# Prototipo_2_0.net
KiCad netlist of a schematic drawn in EAGLE
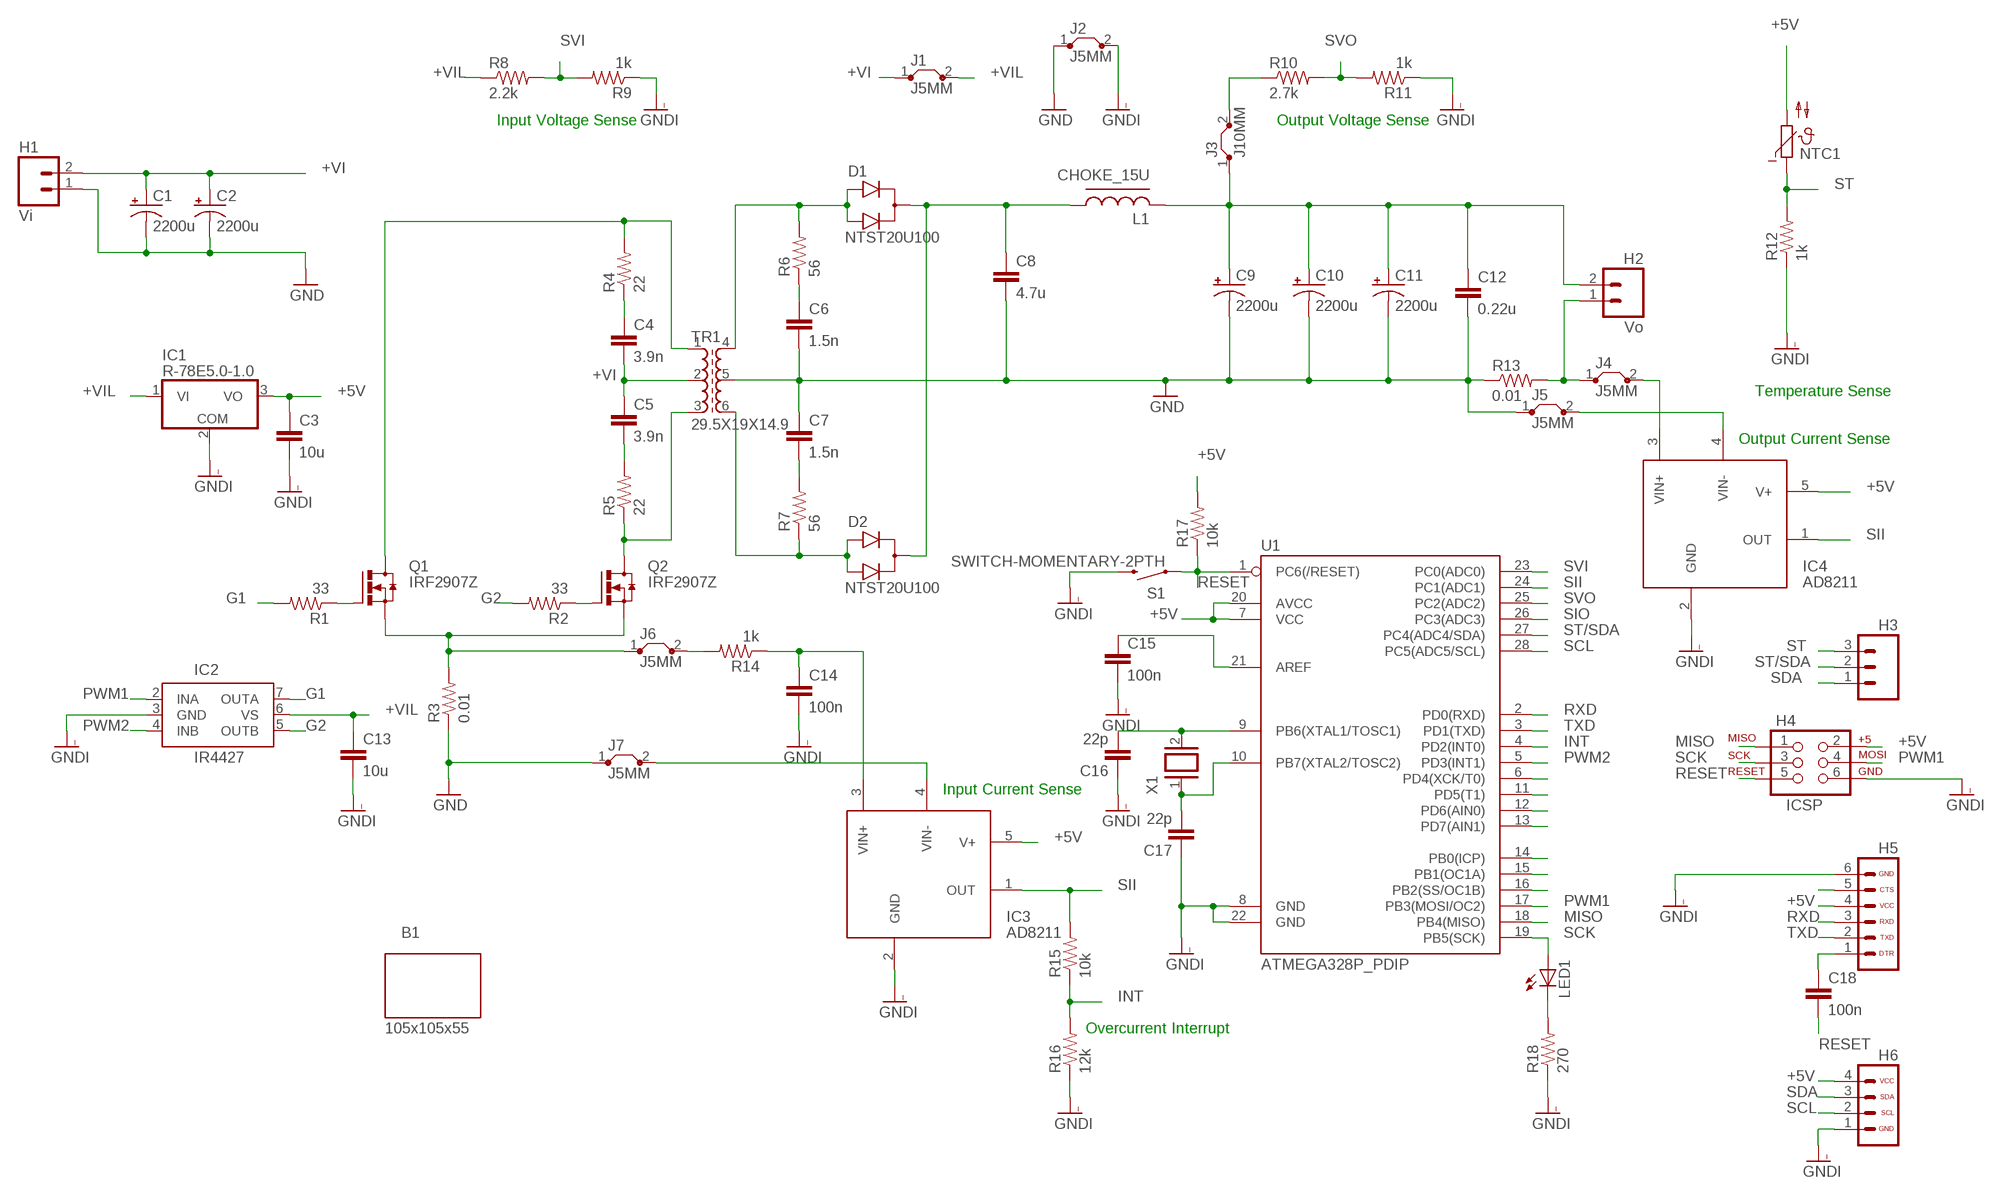
[diagram p0: schematic, sheet 1]

(export (version "E")
  (design (tool "Eeschema 10.0.6"))
  (components
    (comp (ref "B1")
      (value "105x105x55")
      (footprint "eagle-import:BOX_105X105X55")
      (libsource (lib "eagle-import") (part "BOX_105X105X55"))
    )
    (comp (ref "C1")
      (value "2200u")
      (footprint "eagle-import:CPOL_RADIAL_12.5MM_5MM")
      (libsource (lib "eagle-import") (part "CPOL_12.5MM_5MM"))
    )
    (comp (ref "C2")
      (value "2200u")
      (footprint "eagle-import:CPOL_RADIAL_12.5MM_5MM")
      (libsource (lib "eagle-import") (part "CPOL_12.5MM_5MM"))
    )
    (comp (ref "C3")
      (value "10u")
      (footprint "eagle-import:C5B2.5")
      (libsource (lib "eagle-import") (part "C5/2.5"))
    )
    (comp (ref "C4")
      (value "3.9n")
      (footprint "eagle-import:C7.5B3")
      (libsource (lib "eagle-import") (part "C7.5/3"))
    )
    (comp (ref "C5")
      (value "3.9n")
      (footprint "eagle-import:C7.5B3")
      (libsource (lib "eagle-import") (part "C7.5/3"))
    )
    (comp (ref "C6")
      (value "1.5n")
      (footprint "eagle-import:C7.5B3")
      (libsource (lib "eagle-import") (part "C7.5/3"))
    )
    (comp (ref "C7")
      (value "1.5n")
      (footprint "eagle-import:C7.5B3")
      (libsource (lib "eagle-import") (part "C7.5/3"))
    )
    (comp (ref "C8")
      (value "4.7u")
      (footprint "eagle-import:C5B2.5")
      (libsource (lib "eagle-import") (part "C5/2.5"))
    )
    (comp (ref "C9")
      (value "2200u")
      (footprint "eagle-import:CPOL_RADIAL_12.5MM_5MM")
      (libsource (lib "eagle-import") (part "CPOL_12.5MM_5MM"))
    )
    (comp (ref "C10")
      (value "2200u")
      (footprint "eagle-import:CPOL_RADIAL_12.5MM_5MM")
      (libsource (lib "eagle-import") (part "CPOL_12.5MM_5MM"))
    )
    (comp (ref "C11")
      (value "2200u")
      (footprint "eagle-import:CPOL_RADIAL_12.5MM_5MM")
      (libsource (lib "eagle-import") (part "CPOL_12.5MM_5MM"))
    )
    (comp (ref "C12")
      (value "0.22u")
      (footprint "eagle-import:C5B3")
      (libsource (lib "eagle-import") (part "C5/3"))
    )
    (comp (ref "C13")
      (value "10u")
      (footprint "eagle-import:C5B2.5")
      (libsource (lib "eagle-import") (part "C5/2.5"))
    )
    (comp (ref "C14")
      (value "100n")
      (footprint "eagle-import:C5B3")
      (libsource (lib "eagle-import") (part "C5/3"))
    )
    (comp (ref "C15")
      (value "100n")
      (footprint "eagle-import:C5B3")
      (libsource (lib "eagle-import") (part "C5/3"))
    )
    (comp (ref "C16")
      (value "22p")
      (footprint "eagle-import:C5B2.5")
      (libsource (lib "eagle-import") (part "C5/2.5"))
    )
    (comp (ref "C17")
      (value "22p")
      (footprint "eagle-import:C5B2.5")
      (libsource (lib "eagle-import") (part "C5/2.5"))
    )
    (comp (ref "C18")
      (value "100n")
      (footprint "eagle-import:C5B3")
      (libsource (lib "eagle-import") (part "C5/3"))
    )
    (comp (ref "D1")
      (value "NTST20U100")
      (footprint "eagle-import:TO220V")
      (libsource (lib "eagle-import") (part "NTST20U100CTG"))
    )
    (comp (ref "D2")
      (value "NTST20U100")
      (footprint "eagle-import:TO220V")
      (libsource (lib "eagle-import") (part "NTST20U100CTG"))
    )
    (comp (ref "H1")
      (value "Vi")
      (footprint "eagle-import:SCREWTERMINAL-5MM-2")
      (libsource (lib "eagle-import") (part "M025MM"))
    )
    (comp (ref "H2")
      (value "Vo")
      (footprint "eagle-import:SCREWTERMINAL-5MM-2")
      (libsource (lib "eagle-import") (part "M025MM"))
    )
    (comp (ref "H3")
      (value "M03PTH")
      (footprint "eagle-import:1X03")
      (libsource (lib "eagle-import") (part "M03PTH"))
    )
    (comp (ref "H4")
      (value "ICSP")
      (footprint "eagle-import:2X3")
      (libsource (lib "eagle-import") (part "AVR_SPI_PRG_6PTH"))
    )
    (comp (ref "H5")
      (value "HEADER_SERIAL")
      (footprint "eagle-import:HEADER_SERIAL")
      (libsource (lib "eagle-import") (part "HEADER_SERIAL"))
    )
    (comp (ref "H6")
      (value "HEADER_I2C")
      (footprint "eagle-import:HEADER_I2C")
      (libsource (lib "eagle-import") (part "HEADER_I2C"))
    )
    (comp (ref "IC1")
      (value "R-78E5.0-1.0")
      (footprint "eagle-import:R-78E5.0-1.0")
      (libsource (lib "eagle-import") (part "R-78E5.0-1.0"))
    )
    (comp (ref "IC2")
      (value "IR4427")
      (footprint "eagle-import:DIL08")
      (libsource (lib "eagle-import") (part "IR4427"))
    )
    (comp (ref "IC3")
      (value "AD8211")
      (footprint "eagle-import:RJ-5")
      (libsource (lib "eagle-import") (part "AD8211"))
    )
    (comp (ref "IC4")
      (value "AD8211")
      (footprint "eagle-import:RJ-5")
      (libsource (lib "eagle-import") (part "AD8211"))
    )
    (comp (ref "J1")
      (value "J5MM")
      (footprint "eagle-import:05")
      (libsource (lib "eagle-import") (part "J5MM"))
    )
    (comp (ref "J2")
      (value "J5MM")
      (footprint "eagle-import:05")
      (libsource (lib "eagle-import") (part "J5MM"))
    )
    (comp (ref "J3")
      (value "J10MM")
      (footprint "eagle-import:10")
      (libsource (lib "eagle-import") (part "J10MM"))
    )
    (comp (ref "J4")
      (value "J5MM")
      (footprint "eagle-import:05")
      (libsource (lib "eagle-import") (part "J5MM"))
    )
    (comp (ref "J5")
      (value "J5MM")
      (footprint "eagle-import:05")
      (libsource (lib "eagle-import") (part "J5MM"))
    )
    (comp (ref "J6")
      (value "J5MM")
      (footprint "eagle-import:05")
      (libsource (lib "eagle-import") (part "J5MM"))
    )
    (comp (ref "J7")
      (value "J5MM")
      (footprint "eagle-import:05")
      (libsource (lib "eagle-import") (part "J5MM"))
    )
    (comp (ref "L1")
      (value "CHOKE_15U")
      (footprint "eagle-import:CHOKE_15U")
      (libsource (lib "eagle-import") (part "CHOKE_15U"))
    )
    (comp (ref "LED1")
      (value "LED5MM")
      (footprint "eagle-import:LED5MM")
      (libsource (lib "eagle-import") (part "LED5MM"))
    )
    (comp (ref "NTC1")
      (value "NTC640")
      (footprint "eagle-import:P640")
      (fields (field (name "OC_FARNELL") "unknown") (field (name "OC_NEWARK") "unknown"))
      (libsource (lib "eagle-import") (part "NTC640"))
    )
    (comp (ref "Q1")
      (value "IRF2907Z")
      (footprint "eagle-import:TO220V")
      (libsource (lib "eagle-import") (part "IRF2907Z"))
    )
    (comp (ref "Q2")
      (value "IRF2907Z")
      (footprint "eagle-import:TO220V")
      (libsource (lib "eagle-import") (part "IRF2907Z"))
    )
    (comp (ref "R1")
      (value "33")
      (footprint "eagle-import:AXIAL-0.4")
      (libsource (lib "eagle-import") (part "RESISTORPTH-1/4W"))
    )
    (comp (ref "R2")
      (value "33")
      (footprint "eagle-import:AXIAL-0.4")
      (libsource (lib "eagle-import") (part "RESISTORPTH-1/4W"))
    )
    (comp (ref "R3")
      (value "0.01")
      (footprint "eagle-import:RSENSE")
      (libsource (lib "eagle-import") (part "RSENSE"))
    )
    (comp (ref "R4")
      (value "22")
      (footprint "eagle-import:AXIAL-0.5")
      (libsource (lib "eagle-import") (part "RESISTORPTH-1/2W"))
    )
    (comp (ref "R5")
      (value "22")
      (footprint "eagle-import:AXIAL-0.5")
      (libsource (lib "eagle-import") (part "RESISTORPTH-1/2W"))
    )
    (comp (ref "R6")
      (value "56")
      (footprint "eagle-import:AXIAL-0.5")
      (libsource (lib "eagle-import") (part "RESISTORPTH-1/2W"))
    )
    (comp (ref "R7")
      (value "56")
      (footprint "eagle-import:AXIAL-0.5")
      (libsource (lib "eagle-import") (part "RESISTORPTH-1/2W"))
    )
    (comp (ref "R8")
      (value "2.2k")
      (footprint "eagle-import:AXIAL-0.4")
      (libsource (lib "eagle-import") (part "RESISTORPTH-1/4W"))
    )
    (comp (ref "R9")
      (value "1k")
      (footprint "eagle-import:AXIAL-0.4")
      (libsource (lib "eagle-import") (part "RESISTORPTH-1/4W"))
    )
    (comp (ref "R10")
      (value "2.7k")
      (footprint "eagle-import:AXIAL-0.4")
      (libsource (lib "eagle-import") (part "RESISTORPTH-1/4W"))
    )
    (comp (ref "R11")
      (value "1k")
      (footprint "eagle-import:AXIAL-0.4")
      (libsource (lib "eagle-import") (part "RESISTORPTH-1/4W"))
    )
    (comp (ref "R12")
      (value "1k")
      (footprint "eagle-import:AXIAL-0.4")
      (libsource (lib "eagle-import") (part "RESISTORPTH-1/4W"))
    )
    (comp (ref "R13")
      (value "0.01")
      (footprint "eagle-import:RSENSE")
      (libsource (lib "eagle-import") (part "RSENSE"))
    )
    (comp (ref "R14")
      (value "1k")
      (footprint "eagle-import:AXIAL-0.4")
      (libsource (lib "eagle-import") (part "RESISTORPTH-1/4W"))
    )
    (comp (ref "R15")
      (value "10k")
      (footprint "eagle-import:AXIAL-0.4")
      (libsource (lib "eagle-import") (part "RESISTORPTH-1/4W"))
    )
    (comp (ref "R16")
      (value "12k")
      (footprint "eagle-import:AXIAL-0.4")
      (libsource (lib "eagle-import") (part "RESISTORPTH-1/4W"))
    )
    (comp (ref "R17")
      (value "10k")
      (footprint "eagle-import:AXIAL-0.4")
      (libsource (lib "eagle-import") (part "RESISTORPTH-1/4W"))
    )
    (comp (ref "R18")
      (value "270")
      (footprint "eagle-import:AXIAL-0.4")
      (libsource (lib "eagle-import") (part "RESISTORPTH-1/4W"))
    )
    (comp (ref "S1")
      (value "SWITCH-MOMENTARY-2PTH")
      (footprint "eagle-import:TACTILE-PTH")
      (libsource (lib "eagle-import") (part "SWITCH-MOMENTARY-2PTH"))
    )
    (comp (ref "TR1")
      (value "29.5X19X14.9")
      (footprint "eagle-import:CORE_29.5X19X14.9")
      (libsource (lib "eagle-import") (part "29.5X19X14.9_N87"))
    )
    (comp (ref "U1")
      (value "ATMEGA328P_PDIP")
      (footprint "eagle-import:DIL28-3")
      (libsource (lib "eagle-import") (part "ATMEGA328P_PDIP"))
    )
    (comp (ref "X1")
      (value "XTAL/S")
      (footprint "eagle-import:QS")
      (libsource (lib "eagle-import") (part "XTAL/S"))
    )
  )
  (nets
    (net (code "1") (name "/+5V") (class "Default")
      (node (ref "C3") (pin "1") (pinfunction "1_1") (pintype "passive"))
      (node (ref "H4") (pin "2") (pinfunction "2_2") (pintype "passive"))
      (node (ref "H5") (pin "4") (pinfunction "4_VCC_4") (pintype "passive"))
      (node (ref "H6") (pin "4") (pinfunction "4_VCC_4") (pintype "passive"))
      (node (ref "IC1") (pin "3") (pinfunction "VO_3") (pintype "power_in"))
      (node (ref "IC3") (pin "5") (pinfunction "V+_5") (pintype "bidirectional"))
      (node (ref "IC4") (pin "5") (pinfunction "V+_5") (pintype "bidirectional"))
      (node (ref "NTC1") (pin "2") (pinfunction "2_2") (pintype "passive"))
      (node (ref "R17") (pin "P$2") (pinfunction "2_P$2") (pintype "passive"))
      (node (ref "U1") (pin "20") (pinfunction "AVCC_20") (pintype "bidirectional"))
      (node (ref "U1") (pin "7") (pinfunction "VCC_7") (pintype "bidirectional"))
    )
    (net (code "2") (name "/+VI") (class "Default")
      (node (ref "C1") (pin "+") (pinfunction "+_+") (pintype "passive"))
      (node (ref "C2") (pin "+") (pinfunction "+_+") (pintype "passive"))
      (node (ref "C4") (pin "2") (pinfunction "2_2") (pintype "passive"))
      (node (ref "C5") (pin "1") (pinfunction "1_1") (pintype "passive"))
      (node (ref "H1") (pin "2") (pinfunction "2_2") (pintype "passive"))
      (node (ref "J1") (pin "1") (pinfunction "1_1") (pintype "passive"))
      (node (ref "TR1") (pin "2") (pinfunction "2_2") (pintype "passive"))
    )
    (net (code "3") (name "/+VIL") (class "Default")
      (node (ref "C13") (pin "1") (pinfunction "1_1") (pintype "passive"))
      (node (ref "IC1") (pin "1") (pinfunction "VI_1") (pintype "power_in"))
      (node (ref "IC2") (pin "6") (pinfunction "VS_6") (pintype "bidirectional"))
      (node (ref "J1") (pin "2") (pinfunction "2_2") (pintype "passive"))
      (node (ref "R8") (pin "P$1") (pinfunction "1_P$1") (pintype "passive"))
    )
    (net (code "4") (name "/G1") (class "Default")
      (node (ref "IC2") (pin "7") (pinfunction "OUTA_7") (pintype "bidirectional"))
      (node (ref "R1") (pin "P$2") (pinfunction "2_P$2") (pintype "passive"))
    )
    (net (code "5") (name "/G2") (class "Default")
      (node (ref "IC2") (pin "5") (pinfunction "OUTB_5") (pintype "bidirectional"))
      (node (ref "R2") (pin "P$2") (pinfunction "2_P$2") (pintype "passive"))
    )
    (net (code "6") (name "/INT") (class "Default")
      (node (ref "R15") (pin "P$1") (pinfunction "1_P$1") (pintype "passive"))
      (node (ref "R16") (pin "P$2") (pinfunction "2_P$2") (pintype "passive"))
      (node (ref "U1") (pin "4") (pinfunction "PD2(INT0)_4") (pintype "bidirectional"))
    )
    (net (code "7") (name "/MISO") (class "Default")
      (node (ref "H4") (pin "1") (pinfunction "1_1") (pintype "passive"))
      (node (ref "U1") (pin "18") (pinfunction "PB4(MISO)_18") (pintype "bidirectional"))
    )
    (net (code "8") (name "/PWM1") (class "Default")
      (node (ref "H4") (pin "4") (pinfunction "4_4") (pintype "passive"))
      (node (ref "IC2") (pin "2") (pinfunction "INA_2") (pintype "bidirectional"))
      (node (ref "U1") (pin "17") (pinfunction "PB3(MOSI/OC2)_17") (pintype "bidirectional"))
    )
    (net (code "9") (name "/PWM2") (class "Default")
      (node (ref "IC2") (pin "4") (pinfunction "INB_4") (pintype "bidirectional"))
      (node (ref "U1") (pin "5") (pinfunction "PD3(INT1)_5") (pintype "bidirectional"))
    )
    (net (code "10") (name "/RESET") (class "Default")
      (node (ref "C18") (pin "2") (pinfunction "2_2") (pintype "passive"))
      (node (ref "H4") (pin "5") (pinfunction "5_5") (pintype "passive"))
      (node (ref "R17") (pin "P$1") (pinfunction "1_P$1") (pintype "passive"))
      (node (ref "S1") (pin "1") (pinfunction "1_1") (pintype "passive"))
      (node (ref "U1") (pin "1") (pinfunction "PC6(/RESET)_1") (pintype "bidirectional"))
    )
    (net (code "11") (name "/RXD") (class "Default")
      (node (ref "H5") (pin "3") (pinfunction "3_RXD_3") (pintype "passive"))
      (node (ref "U1") (pin "2") (pinfunction "PD0(RXD)_2") (pintype "bidirectional"))
    )
    (net (code "12") (name "/SCK") (class "Default")
      (node (ref "H4") (pin "3") (pinfunction "3_3") (pintype "passive"))
      (node (ref "LED1") (pin "A") (pinfunction "A_A") (pintype "passive"))
      (node (ref "U1") (pin "19") (pinfunction "PB5(SCK)_19") (pintype "bidirectional"))
    )
    (net (code "13") (name "/SCL") (class "Default")
      (node (ref "H6") (pin "2") (pinfunction "2_SCL_2") (pintype "passive"))
      (node (ref "U1") (pin "28") (pinfunction "PC5(ADC5/SCL)_28") (pintype "bidirectional"))
    )
    (net (code "14") (name "/SDA") (class "Default")
      (node (ref "H3") (pin "1") (pinfunction "1_1") (pintype "passive"))
      (node (ref "H6") (pin "3") (pinfunction "3_SDA_3") (pintype "passive"))
    )
    (net (code "15") (name "/SII") (class "Default")
      (node (ref "IC3") (pin "1") (pinfunction "OUT_1") (pintype "bidirectional"))
      (node (ref "IC4") (pin "1") (pinfunction "OUT_1") (pintype "bidirectional"))
      (node (ref "R15") (pin "P$2") (pinfunction "2_P$2") (pintype "passive"))
      (node (ref "U1") (pin "24") (pinfunction "PC1(ADC1)_24") (pintype "bidirectional"))
    )
    (net (code "16") (name "/SIO") (class "Default")
      (node (ref "U1") (pin "26") (pinfunction "PC3(ADC3)_26") (pintype "bidirectional"))
    )
    (net (code "17") (name "/ST") (class "Default")
      (node (ref "H3") (pin "3") (pinfunction "3_3") (pintype "passive"))
      (node (ref "NTC1") (pin "1") (pinfunction "1_1") (pintype "passive"))
      (node (ref "R12") (pin "P$2") (pinfunction "2_P$2") (pintype "passive"))
    )
    (net (code "18") (name "/ST{slash}SDA") (class "Default")
      (node (ref "H3") (pin "2") (pinfunction "2_2") (pintype "passive"))
      (node (ref "U1") (pin "27") (pinfunction "PC4(ADC4/SDA)_27") (pintype "bidirectional"))
    )
    (net (code "19") (name "/SVI") (class "Default")
      (node (ref "R8") (pin "P$2") (pinfunction "2_P$2") (pintype "passive"))
      (node (ref "R9") (pin "P$2") (pinfunction "2_P$2") (pintype "passive"))
      (node (ref "U1") (pin "23") (pinfunction "PC0(ADC0)_23") (pintype "bidirectional"))
    )
    (net (code "20") (name "/SVO") (class "Default")
      (node (ref "R10") (pin "P$2") (pinfunction "2_P$2") (pintype "passive"))
      (node (ref "R11") (pin "P$2") (pinfunction "2_P$2") (pintype "passive"))
      (node (ref "U1") (pin "25") (pinfunction "PC2(ADC2)_25") (pintype "bidirectional"))
    )
    (net (code "21") (name "/TXD") (class "Default")
      (node (ref "H5") (pin "2") (pinfunction "2_TXD_2") (pintype "passive"))
      (node (ref "U1") (pin "3") (pinfunction "PD1(TXD)_3") (pintype "bidirectional"))
    )
    (net (code "22") (name "GND") (class "Default")
      (node (ref "C1") (pin "-") (pinfunction "-_-") (pintype "passive"))
      (node (ref "C10") (pin "-") (pinfunction "-_-") (pintype "passive"))
      (node (ref "C11") (pin "-") (pinfunction "-_-") (pintype "passive"))
      (node (ref "C12") (pin "2") (pinfunction "2_2") (pintype "passive"))
      (node (ref "C2") (pin "-") (pinfunction "-_-") (pintype "passive"))
      (node (ref "C6") (pin "2") (pinfunction "2_2") (pintype "passive"))
      (node (ref "C7") (pin "1") (pinfunction "1_1") (pintype "passive"))
      (node (ref "C8") (pin "2") (pinfunction "2_2") (pintype "passive"))
      (node (ref "C9") (pin "-") (pinfunction "-_-") (pintype "passive"))
      (node (ref "H1") (pin "1") (pinfunction "1_1") (pintype "passive"))
      (node (ref "J2") (pin "1") (pinfunction "1_1") (pintype "passive"))
      (node (ref "J5") (pin "1") (pinfunction "1_1") (pintype "passive"))
      (node (ref "J7") (pin "1") (pinfunction "1_1") (pintype "passive"))
      (node (ref "R13") (pin "P$1") (pinfunction "1_P$1") (pintype "passive"))
      (node (ref "R3") (pin "P$1") (pinfunction "1_P$1") (pintype "passive"))
      (node (ref "TR1") (pin "5") (pinfunction "5_5") (pintype "passive"))
    )
    (net (code "23") (name "GNDI") (class "Default")
      (node (ref "C13") (pin "2") (pinfunction "2_2") (pintype "passive"))
      (node (ref "C14") (pin "2") (pinfunction "2_2") (pintype "passive"))
      (node (ref "C15") (pin "2") (pinfunction "2_2") (pintype "passive"))
      (node (ref "C16") (pin "1") (pinfunction "1_1") (pintype "passive"))
      (node (ref "C17") (pin "1") (pinfunction "1_1") (pintype "passive"))
      (node (ref "C3") (pin "2") (pinfunction "2_2") (pintype "passive"))
      (node (ref "H4") (pin "6") (pinfunction "6_6") (pintype "passive"))
      (node (ref "H5") (pin "6") (pinfunction "6_GND_6") (pintype "passive"))
      (node (ref "H6") (pin "1") (pinfunction "1_GND_1") (pintype "passive"))
      (node (ref "IC1") (pin "2") (pinfunction "COM_2") (pintype "power_in"))
      (node (ref "IC2") (pin "3") (pinfunction "GND_3") (pintype "bidirectional"))
      (node (ref "IC3") (pin "2") (pinfunction "GND_2") (pintype "bidirectional"))
      (node (ref "IC4") (pin "2") (pinfunction "GND_2") (pintype "bidirectional"))
      (node (ref "J2") (pin "2") (pinfunction "2_2") (pintype "passive"))
      (node (ref "R11") (pin "P$1") (pinfunction "1_P$1") (pintype "passive"))
      (node (ref "R12") (pin "P$1") (pinfunction "1_P$1") (pintype "passive"))
      (node (ref "R16") (pin "P$1") (pinfunction "1_P$1") (pintype "passive"))
      (node (ref "R18") (pin "P$1") (pinfunction "1_P$1") (pintype "passive"))
      (node (ref "R9") (pin "P$1") (pinfunction "1_P$1") (pintype "passive"))
      (node (ref "S1") (pin "3") (pinfunction "2_3") (pintype "passive"))
      (node (ref "U1") (pin "22") (pinfunction "GND_22") (pintype "bidirectional"))
      (node (ref "U1") (pin "8") (pinfunction "GND_8") (pintype "bidirectional"))
    )
    (net (code "24") (name "Net-(C10-Pad+)") (class "Default")
      (node (ref "C10") (pin "+") (pinfunction "+_+") (pintype "passive"))
      (node (ref "C11") (pin "+") (pinfunction "+_+") (pintype "passive"))
      (node (ref "C12") (pin "1") (pinfunction "1_1") (pintype "passive"))
      (node (ref "C9") (pin "+") (pinfunction "+_+") (pintype "passive"))
      (node (ref "H2") (pin "2") (pinfunction "2_2") (pintype "passive"))
      (node (ref "J3") (pin "1") (pinfunction "1_1") (pintype "passive"))
      (node (ref "L1") (pin "2") (pinfunction "2_2") (pintype "passive"))
    )
    (net (code "25") (name "Net-(D1-A1)") (class "Default")
      (node (ref "D1") (pin "1") (pinfunction "A1_1") (pintype "passive"))
      (node (ref "D1") (pin "3") (pinfunction "A2_3") (pintype "passive"))
      (node (ref "R6") (pin "P$2") (pinfunction "2_P$2") (pintype "passive"))
      (node (ref "TR1") (pin "4") (pinfunction "4_4") (pintype "passive"))
    )
    (net (code "26") (name "Net-(D1-C)") (class "Default")
      (node (ref "C8") (pin "1") (pinfunction "1_1") (pintype "passive"))
      (node (ref "D1") (pin "2") (pinfunction "C_2") (pintype "passive"))
      (node (ref "D2") (pin "2") (pinfunction "C_2") (pintype "passive"))
      (node (ref "L1") (pin "1") (pinfunction "1_1") (pintype "passive"))
    )
    (net (code "27") (name "Net-(D2-A1)") (class "Default")
      (node (ref "D2") (pin "1") (pinfunction "A1_1") (pintype "passive"))
      (node (ref "D2") (pin "3") (pinfunction "A2_3") (pintype "passive"))
      (node (ref "R7") (pin "P$1") (pinfunction "1_P$1") (pintype "passive"))
      (node (ref "TR1") (pin "6") (pinfunction "6_6") (pintype "passive"))
    )
    (net (code "28") (name "Net-(H5-1_DTR)") (class "Default")
      (node (ref "C18") (pin "1") (pinfunction "1_1") (pintype "passive"))
      (node (ref "H5") (pin "1") (pinfunction "1_DTR_1") (pintype "passive"))
    )
    (net (code "29") (name "Net-(IC3-VIN+)") (class "Default")
      (node (ref "C14") (pin "1") (pinfunction "1_1") (pintype "passive"))
      (node (ref "IC3") (pin "3") (pinfunction "VIN+_3") (pintype "bidirectional"))
      (node (ref "R14") (pin "P$1") (pinfunction "1_P$1") (pintype "passive"))
    )
    (net (code "30") (name "Net-(IC3-VIN-)") (class "Default")
      (node (ref "IC3") (pin "4") (pinfunction "VIN-_4") (pintype "bidirectional"))
      (node (ref "J7") (pin "2") (pinfunction "2_2") (pintype "passive"))
    )
    (net (code "31") (name "Net-(IC4-VIN+)") (class "Default")
      (node (ref "IC4") (pin "3") (pinfunction "VIN+_3") (pintype "bidirectional"))
      (node (ref "J4") (pin "2") (pinfunction "2_2") (pintype "passive"))
    )
    (net (code "32") (name "Net-(IC4-VIN-)") (class "Default")
      (node (ref "IC4") (pin "4") (pinfunction "VIN-_4") (pintype "bidirectional"))
      (node (ref "J5") (pin "2") (pinfunction "2_2") (pintype "passive"))
    )
    (net (code "33") (name "Net-(LED1-C)") (class "Default")
      (node (ref "LED1") (pin "K") (pinfunction "C_K") (pintype "passive"))
      (node (ref "R18") (pin "P$2") (pinfunction "2_P$2") (pintype "passive"))
    )
    (net (code "34") (name "Net-(Q1-D)") (class "Default")
      (node (ref "Q1") (pin "2") (pinfunction "D_2") (pintype "passive"))
      (node (ref "R4") (pin "P$2") (pinfunction "2_P$2") (pintype "passive"))
      (node (ref "TR1") (pin "1") (pinfunction "1_1") (pintype "passive"))
    )
    (net (code "35") (name "Net-(Q1-G)") (class "Default")
      (node (ref "Q1") (pin "1") (pinfunction "G_1") (pintype "passive"))
      (node (ref "R1") (pin "P$1") (pinfunction "1_P$1") (pintype "passive"))
    )
    (net (code "36") (name "Net-(Q1-S)") (class "Default")
      (node (ref "J6") (pin "1") (pinfunction "1_1") (pintype "passive"))
      (node (ref "Q1") (pin "3") (pinfunction "S_3") (pintype "passive"))
      (node (ref "Q2") (pin "3") (pinfunction "S_3") (pintype "passive"))
      (node (ref "R3") (pin "P$2") (pinfunction "2_P$2") (pintype "passive"))
    )
    (net (code "37") (name "Net-(Q2-D)") (class "Default")
      (node (ref "Q2") (pin "2") (pinfunction "D_2") (pintype "passive"))
      (node (ref "R5") (pin "P$1") (pinfunction "1_P$1") (pintype "passive"))
      (node (ref "TR1") (pin "3") (pinfunction "3_3") (pintype "passive"))
    )
    (net (code "38") (name "Net-(Q2-G)") (class "Default")
      (node (ref "Q2") (pin "1") (pinfunction "G_1") (pintype "passive"))
      (node (ref "R2") (pin "P$1") (pinfunction "1_P$1") (pintype "passive"))
    )
    (net (code "39") (name "Net-(R4-1)") (class "Default")
      (node (ref "C4") (pin "1") (pinfunction "1_1") (pintype "passive"))
      (node (ref "R4") (pin "P$1") (pinfunction "1_P$1") (pintype "passive"))
    )
    (net (code "40") (name "Net-(R5-2)") (class "Default")
      (node (ref "C5") (pin "2") (pinfunction "2_2") (pintype "passive"))
      (node (ref "R5") (pin "P$2") (pinfunction "2_P$2") (pintype "passive"))
    )
    (net (code "41") (name "Net-(R6-1)") (class "Default")
      (node (ref "C6") (pin "1") (pinfunction "1_1") (pintype "passive"))
      (node (ref "R6") (pin "P$1") (pinfunction "1_P$1") (pintype "passive"))
    )
    (net (code "42") (name "Net-(R7-2)") (class "Default")
      (node (ref "C7") (pin "2") (pinfunction "2_2") (pintype "passive"))
      (node (ref "R7") (pin "P$2") (pinfunction "2_P$2") (pintype "passive"))
    )
    (net (code "43") (name "Net-(R10-1)") (class "Default")
      (node (ref "J3") (pin "2") (pinfunction "2_2") (pintype "passive"))
      (node (ref "R10") (pin "P$1") (pinfunction "1_P$1") (pintype "passive"))
    )
    (net (code "44") (name "Net-(R13-2)") (class "Default")
      (node (ref "H2") (pin "1") (pinfunction "1_1") (pintype "passive"))
      (node (ref "J4") (pin "1") (pinfunction "1_1") (pintype "passive"))
      (node (ref "R13") (pin "P$2") (pinfunction "2_P$2") (pintype "passive"))
    )
    (net (code "45") (name "Net-(R14-2)") (class "Default")
      (node (ref "J6") (pin "2") (pinfunction "2_2") (pintype "passive"))
      (node (ref "R14") (pin "P$2") (pinfunction "2_P$2") (pintype "passive"))
    )
    (net (code "46") (name "Net-(U1-AREF)") (class "Default")
      (node (ref "C15") (pin "1") (pinfunction "1_1") (pintype "passive"))
      (node (ref "U1") (pin "21") (pinfunction "AREF_21") (pintype "bidirectional"))
    )
    (net (code "47") (name "Net-(U1-PB6(XTAL1{slash}TOSC1))") (class "Default")
      (node (ref "C16") (pin "2") (pinfunction "2_2") (pintype "passive"))
      (node (ref "U1") (pin "9") (pinfunction "PB6(XTAL1/TOSC1)_9") (pintype "bidirectional"))
      (node (ref "X1") (pin "2") (pinfunction "2_2") (pintype "passive"))
    )
    (net (code "48") (name "Net-(U1-PB7(XTAL2{slash}TOSC2))") (class "Default")
      (node (ref "C17") (pin "2") (pinfunction "2_2") (pintype "passive"))
      (node (ref "U1") (pin "10") (pinfunction "PB7(XTAL2/TOSC2)_10") (pintype "bidirectional"))
      (node (ref "X1") (pin "1") (pinfunction "1_1") (pintype "passive"))
    )
    (net (code "49") (name "unconnected-(H5-5_CTS-Pad5)") (class "Default")
      (node (ref "H5") (pin "5") (pinfunction "5_CTS_5") (pintype "passive"))
    )
    (net (code "50") (name "unconnected-(U1-PB0(ICP)-Pad14)") (class "Default")
      (node (ref "U1") (pin "14") (pinfunction "PB0(ICP)_14") (pintype "bidirectional"))
    )
    (net (code "51") (name "unconnected-(U1-PB1(OC1A)-Pad15)") (class "Default")
      (node (ref "U1") (pin "15") (pinfunction "PB1(OC1A)_15") (pintype "bidirectional"))
    )
    (net (code "52") (name "unconnected-(U1-PB2(SS{slash}OC1B)-Pad16)") (class "Default")
      (node (ref "U1") (pin "16") (pinfunction "PB2(SS/OC1B)_16") (pintype "bidirectional"))
    )
    (net (code "53") (name "unconnected-(U1-PD4(XCK{slash}T0)-Pad6)") (class "Default")
      (node (ref "U1") (pin "6") (pinfunction "PD4(XCK/T0)_6") (pintype "bidirectional"))
    )
    (net (code "54") (name "unconnected-(U1-PD5(T1)-Pad11)") (class "Default")
      (node (ref "U1") (pin "11") (pinfunction "PD5(T1)_11") (pintype "bidirectional"))
    )
    (net (code "55") (name "unconnected-(U1-PD6(AIN0)-Pad12)") (class "Default")
      (node (ref "U1") (pin "12") (pinfunction "PD6(AIN0)_12") (pintype "bidirectional"))
    )
    (net (code "56") (name "unconnected-(U1-PD7(AIN1)-Pad13)") (class "Default")
      (node (ref "U1") (pin "13") (pinfunction "PD7(AIN1)_13") (pintype "bidirectional"))
    )
  )
)
